# SWITCHING.net
KiCad netlist of a schematic drawn in Altium Designer
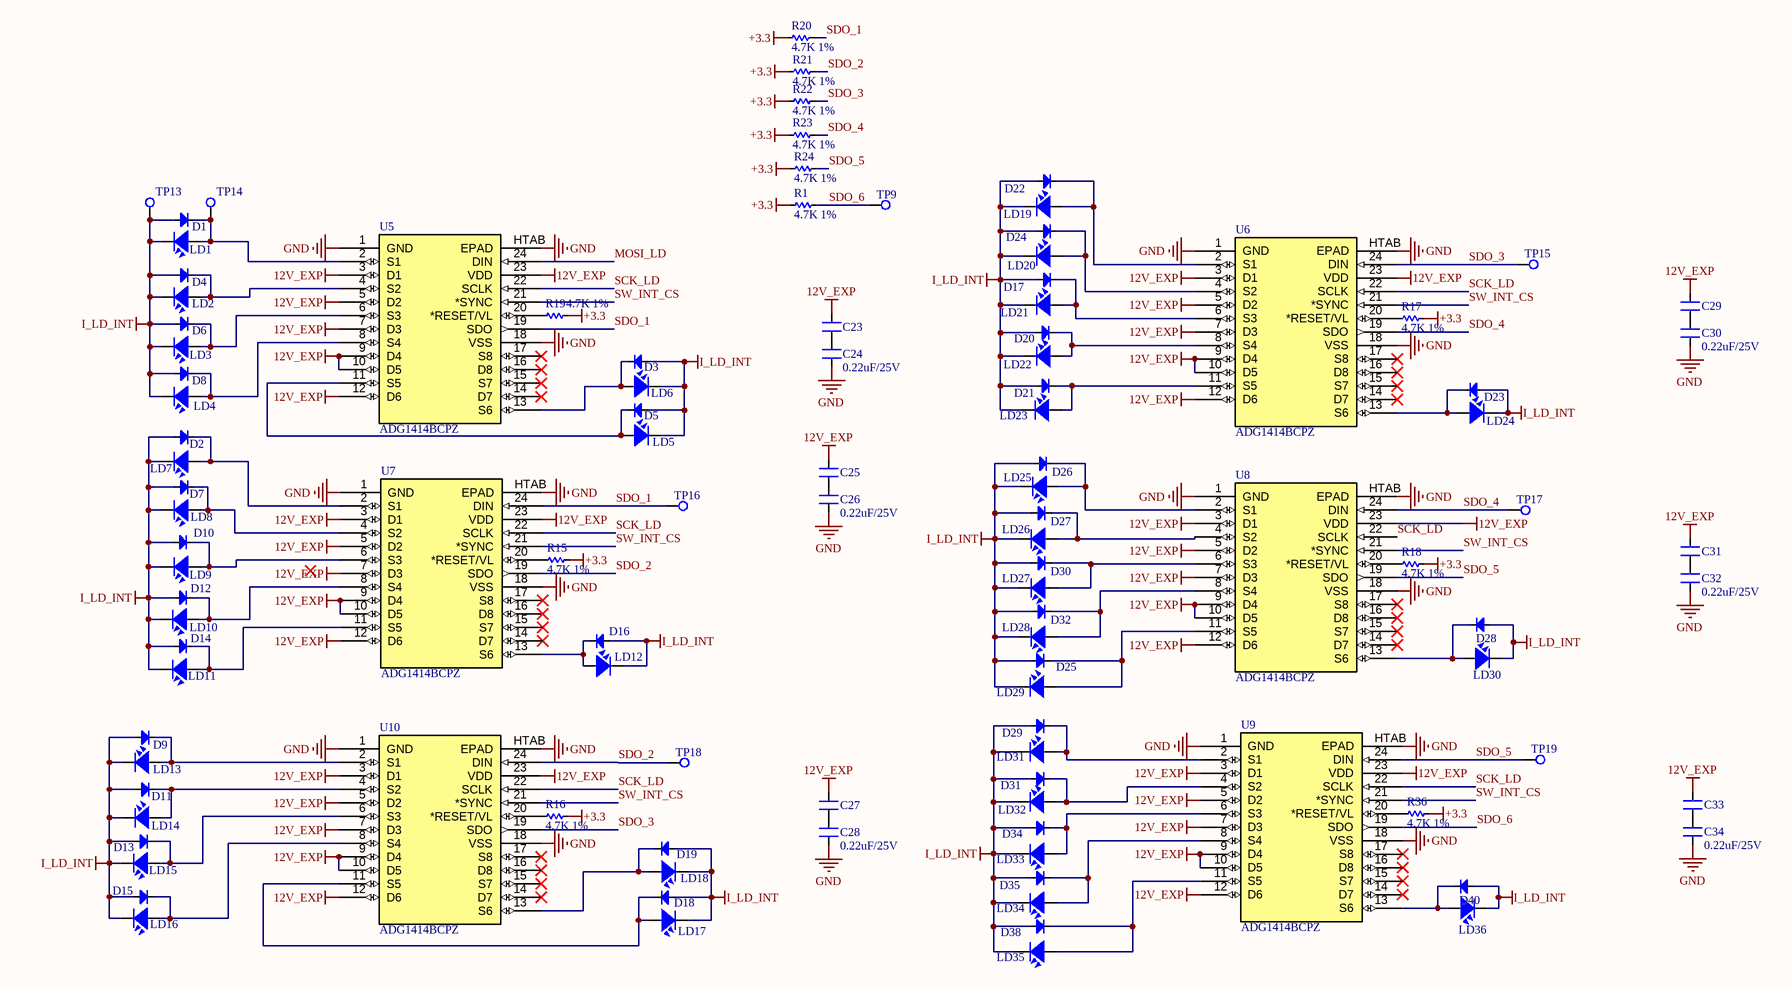
[diagram p0: SWITCHING.SchDoc]

(export (version "E")
  (design (tool "Eeschema 10.0.6"))
  (components
    (comp (ref "C23")
      (value "0.22uF/25V")
      (footprint "SM-0603")
      (description "0603")
      (libsource (lib "Capacitors") (part "CM"))
    )
    (comp (ref "C24")
      (value "0.22uF/25V")
      (footprint "SM-0603")
      (description "0603")
      (libsource (lib "Capacitors") (part "CM"))
    )
    (comp (ref "C25")
      (value "0.22uF/25V")
      (footprint "SM-0603")
      (description "0603")
      (libsource (lib "Capacitors") (part "CM"))
    )
    (comp (ref "C26")
      (value "0.22uF/25V")
      (footprint "SM-0603")
      (description "0603")
      (libsource (lib "Capacitors") (part "CM"))
    )
    (comp (ref "C27")
      (value "0.22uF/25V")
      (footprint "SM-0603")
      (description "0603")
      (libsource (lib "Capacitors") (part "CM"))
    )
    (comp (ref "C28")
      (value "0.22uF/25V")
      (footprint "SM-0603")
      (description "0603")
      (libsource (lib "Capacitors") (part "CM"))
    )
    (comp (ref "C29")
      (value "0.22uF/25V")
      (footprint "SM-0603")
      (description "0603")
      (libsource (lib "Capacitors") (part "CM"))
    )
    (comp (ref "C30")
      (value "0.22uF/25V")
      (footprint "SM-0603")
      (description "0603")
      (libsource (lib "Capacitors") (part "CM"))
    )
    (comp (ref "C31")
      (value "0.22uF/25V")
      (footprint "SM-0603")
      (description "0603")
      (libsource (lib "Capacitors") (part "CM"))
    )
    (comp (ref "C32")
      (value "0.22uF/25V")
      (footprint "SM-0603")
      (description "0603")
      (libsource (lib "Capacitors") (part "CM"))
    )
    (comp (ref "C33")
      (value "0.22uF/25V")
      (footprint "SM-0603")
      (description "0603")
      (libsource (lib "Capacitors") (part "CM"))
    )
    (comp (ref "C34")
      (value "0.22uF/25V")
      (footprint "SM-0603")
      (description "0603")
      (libsource (lib "Capacitors") (part "CM"))
    )
    (comp (ref "D1")
      (value "1N4148W-TP")
      (footprint "SOD23")
      (description "DIODE GEN PURP 100V 150MA SOD123")
      (fields (field (name "PUBLISHER") "Altium Limited"))
      (libsource (lib "Library") (part "Diode SMD"))
    )
    (comp (ref "D2")
      (value "1N4148W-TP")
      (footprint "SOD23")
      (description "DIODE GEN PURP 100V 150MA SOD123")
      (fields (field (name "PUBLISHER") "Altium Limited"))
      (libsource (lib "Library") (part "Diode SMD"))
    )
    (comp (ref "D3")
      (value "1N4148W-TP")
      (footprint "SOD23")
      (description "DIODE GEN PURP 100V 150MA SOD123")
      (fields (field (name "PUBLISHER") "Altium Limited"))
      (libsource (lib "Library") (part "Diode SMD"))
    )
    (comp (ref "D4")
      (value "1N4148W-TP")
      (footprint "SOD23")
      (description "DIODE GEN PURP 100V 150MA SOD123")
      (fields (field (name "PUBLISHER") "Altium Limited"))
      (libsource (lib "Library") (part "Diode SMD"))
    )
    (comp (ref "D5")
      (value "1N4148W-TP")
      (footprint "SOD23")
      (description "DIODE GEN PURP 100V 150MA SOD123")
      (fields (field (name "PUBLISHER") "Altium Limited"))
      (libsource (lib "Library") (part "Diode SMD"))
    )
    (comp (ref "D6")
      (value "1N4148W-TP")
      (footprint "SOD23")
      (description "DIODE GEN PURP 100V 150MA SOD123")
      (fields (field (name "PUBLISHER") "Altium Limited"))
      (libsource (lib "Library") (part "Diode SMD"))
    )
    (comp (ref "D7")
      (value "1N4148W-TP")
      (footprint "SOD23")
      (description "DIODE GEN PURP 100V 150MA SOD123")
      (fields (field (name "PUBLISHER") "Altium Limited"))
      (libsource (lib "Library") (part "Diode SMD"))
    )
    (comp (ref "D8")
      (value "1N4148W-TP")
      (footprint "SOD23")
      (description "DIODE GEN PURP 100V 150MA SOD123")
      (fields (field (name "PUBLISHER") "Altium Limited"))
      (libsource (lib "Library") (part "Diode SMD"))
    )
    (comp (ref "D9")
      (value "1N4148W-TP")
      (footprint "SOD23")
      (description "DIODE GEN PURP 100V 150MA SOD123")
      (fields (field (name "PUBLISHER") "Altium Limited"))
      (libsource (lib "Library") (part "Diode SMD"))
    )
    (comp (ref "D10")
      (value "1N4148W-TP")
      (footprint "SOD23")
      (description "DIODE GEN PURP 100V 150MA SOD123")
      (fields (field (name "PUBLISHER") "Altium Limited"))
      (libsource (lib "Library") (part "Diode SMD"))
    )
    (comp (ref "D11")
      (value "1N4148W-TP")
      (footprint "SOD23")
      (description "DIODE GEN PURP 100V 150MA SOD123")
      (fields (field (name "PUBLISHER") "Altium Limited"))
      (libsource (lib "Library") (part "Diode SMD"))
    )
    (comp (ref "D12")
      (value "1N4148W-TP")
      (footprint "SOD23")
      (description "DIODE GEN PURP 100V 150MA SOD123")
      (fields (field (name "PUBLISHER") "Altium Limited"))
      (libsource (lib "Library") (part "Diode SMD"))
    )
    (comp (ref "D13")
      (value "1N4148W-TP")
      (footprint "SOD23")
      (description "DIODE GEN PURP 100V 150MA SOD123")
      (fields (field (name "PUBLISHER") "Altium Limited"))
      (libsource (lib "Library") (part "Diode SMD"))
    )
    (comp (ref "D14")
      (value "1N4148W-TP")
      (footprint "SOD23")
      (description "DIODE GEN PURP 100V 150MA SOD123")
      (fields (field (name "PUBLISHER") "Altium Limited"))
      (libsource (lib "Library") (part "Diode SMD"))
    )
    (comp (ref "D15")
      (value "1N4148W-TP")
      (footprint "SOD23")
      (description "DIODE GEN PURP 100V 150MA SOD123")
      (fields (field (name "PUBLISHER") "Altium Limited"))
      (libsource (lib "Library") (part "Diode SMD"))
    )
    (comp (ref "D16")
      (value "1N4148W-TP")
      (footprint "SOD23")
      (description "DIODE GEN PURP 100V 150MA SOD123")
      (fields (field (name "PUBLISHER") "Altium Limited"))
      (libsource (lib "Library") (part "Diode SMD"))
    )
    (comp (ref "D17")
      (value "1N4148W-TP")
      (footprint "SOD23")
      (description "DIODE GEN PURP 100V 150MA SOD123")
      (fields (field (name "PUBLISHER") "Altium Limited"))
      (libsource (lib "Library") (part "Diode SMD"))
    )
    (comp (ref "D18")
      (value "1N4148W-TP")
      (footprint "SOD23")
      (description "DIODE GEN PURP 100V 150MA SOD123")
      (fields (field (name "PUBLISHER") "Altium Limited"))
      (libsource (lib "Library") (part "Diode SMD"))
    )
    (comp (ref "D19")
      (value "1N4148W-TP")
      (footprint "SOD23")
      (description "DIODE GEN PURP 100V 150MA SOD123")
      (fields (field (name "PUBLISHER") "Altium Limited"))
      (libsource (lib "Library") (part "Diode SMD"))
    )
    (comp (ref "D20")
      (value "1N4148W-TP")
      (footprint "SOD23")
      (description "DIODE GEN PURP 100V 150MA SOD123")
      (fields (field (name "PUBLISHER") "Altium Limited"))
      (libsource (lib "Library") (part "Diode SMD"))
    )
    (comp (ref "D21")
      (value "1N4148W-TP")
      (footprint "SOD23")
      (description "DIODE GEN PURP 100V 150MA SOD123")
      (fields (field (name "PUBLISHER") "Altium Limited"))
      (libsource (lib "Library") (part "Diode SMD"))
    )
    (comp (ref "D22")
      (value "1N4148W-TP")
      (footprint "SOD23")
      (description "DIODE GEN PURP 100V 150MA SOD123")
      (fields (field (name "PUBLISHER") "Altium Limited"))
      (libsource (lib "Library") (part "Diode SMD"))
    )
    (comp (ref "D23")
      (value "1N4148W-TP")
      (footprint "SOD23")
      (description "DIODE GEN PURP 100V 150MA SOD123")
      (fields (field (name "PUBLISHER") "Altium Limited"))
      (libsource (lib "Library") (part "Diode SMD"))
    )
    (comp (ref "D24")
      (value "1N4148W-TP")
      (footprint "SOD23")
      (description "DIODE GEN PURP 100V 150MA SOD123")
      (fields (field (name "PUBLISHER") "Altium Limited"))
      (libsource (lib "Library") (part "Diode SMD"))
    )
    (comp (ref "D25")
      (value "1N4148W-TP")
      (footprint "SOD23")
      (description "DIODE GEN PURP 100V 150MA SOD123")
      (fields (field (name "PUBLISHER") "Altium Limited"))
      (libsource (lib "Library") (part "Diode SMD"))
    )
    (comp (ref "D26")
      (value "1N4148W-TP")
      (footprint "SOD23")
      (description "DIODE GEN PURP 100V 150MA SOD123")
      (fields (field (name "PUBLISHER") "Altium Limited"))
      (libsource (lib "Library") (part "Diode SMD"))
    )
    (comp (ref "D27")
      (value "1N4148W-TP")
      (footprint "SOD23")
      (description "DIODE GEN PURP 100V 150MA SOD123")
      (fields (field (name "PUBLISHER") "Altium Limited"))
      (libsource (lib "Library") (part "Diode SMD"))
    )
    (comp (ref "D28")
      (value "1N4148W-TP")
      (footprint "SOD23")
      (description "DIODE GEN PURP 100V 150MA SOD123")
      (fields (field (name "PUBLISHER") "Altium Limited"))
      (libsource (lib "Library") (part "Diode SMD"))
    )
    (comp (ref "D29")
      (value "1N4148W-TP")
      (footprint "SOD23")
      (description "DIODE GEN PURP 100V 150MA SOD123")
      (fields (field (name "PUBLISHER") "Altium Limited"))
      (libsource (lib "Library") (part "Diode SMD"))
    )
    (comp (ref "D30")
      (value "1N4148W-TP")
      (footprint "SOD23")
      (description "DIODE GEN PURP 100V 150MA SOD123")
      (fields (field (name "PUBLISHER") "Altium Limited"))
      (libsource (lib "Library") (part "Diode SMD"))
    )
    (comp (ref "D31")
      (value "1N4148W-TP")
      (footprint "SOD23")
      (description "DIODE GEN PURP 100V 150MA SOD123")
      (fields (field (name "PUBLISHER") "Altium Limited"))
      (libsource (lib "Library") (part "Diode SMD"))
    )
    (comp (ref "D32")
      (value "1N4148W-TP")
      (footprint "SOD23")
      (description "DIODE GEN PURP 100V 150MA SOD123")
      (fields (field (name "PUBLISHER") "Altium Limited"))
      (libsource (lib "Library") (part "Diode SMD"))
    )
    (comp (ref "D34")
      (value "1N4148W-TP")
      (footprint "SOD23")
      (description "DIODE GEN PURP 100V 150MA SOD123")
      (fields (field (name "PUBLISHER") "Altium Limited"))
      (libsource (lib "Library") (part "Diode SMD"))
    )
    (comp (ref "D35")
      (value "1N4148W-TP")
      (footprint "SOD23")
      (description "DIODE GEN PURP 100V 150MA SOD123")
      (fields (field (name "PUBLISHER") "Altium Limited"))
      (libsource (lib "Library") (part "Diode SMD"))
    )
    (comp (ref "D38")
      (value "1N4148W-TP")
      (footprint "SOD23")
      (description "DIODE GEN PURP 100V 150MA SOD123")
      (fields (field (name "PUBLISHER") "Altium Limited"))
      (libsource (lib "Library") (part "Diode SMD"))
    )
    (comp (ref "D40")
      (value "1N4148W-TP")
      (footprint "SOD23")
      (description "DIODE GEN PURP 100V 150MA SOD123")
      (fields (field (name "PUBLISHER") "Altium Limited"))
      (libsource (lib "Library") (part "Diode SMD"))
    )
    (comp (ref "LD1")
      (value "LaserDiode")
      (footprint "LASER_SOCKET")
      (libsource (lib "Library_HUNG") (part "LD"))
    )
    (comp (ref "LD2")
      (value "LaserDiode")
      (footprint "LASER_SOCKET")
      (libsource (lib "Library_HUNG") (part "LD"))
    )
    (comp (ref "LD3")
      (value "LaserDiode")
      (footprint "LASER_SOCKET")
      (libsource (lib "Library_HUNG") (part "LD"))
    )
    (comp (ref "LD4")
      (value "LaserDiode")
      (footprint "LASER_SOCKET")
      (libsource (lib "Library_HUNG") (part "LD"))
    )
    (comp (ref "LD5")
      (value "LaserDiode")
      (footprint "LASER_SOCKET")
      (libsource (lib "Library_HUNG") (part "LD"))
    )
    (comp (ref "LD6")
      (value "LaserDiode")
      (footprint "LASER_SOCKET")
      (libsource (lib "Library_HUNG") (part "LD"))
    )
    (comp (ref "LD7")
      (value "LaserDiode")
      (footprint "LASER_SOCKET")
      (libsource (lib "Library_HUNG") (part "LD"))
    )
    (comp (ref "LD8")
      (value "LaserDiode")
      (footprint "LASER_SOCKET")
      (libsource (lib "Library_HUNG") (part "LD"))
    )
    (comp (ref "LD9")
      (value "LaserDiode")
      (footprint "LASER_SOCKET")
      (libsource (lib "Library_HUNG") (part "LD"))
    )
    (comp (ref "LD10")
      (value "LaserDiode")
      (footprint "LASER_SOCKET")
      (libsource (lib "Library_HUNG") (part "LD"))
    )
    (comp (ref "LD11")
      (value "LaserDiode")
      (footprint "LASER_SOCKET")
      (libsource (lib "Library_HUNG") (part "LD"))
    )
    (comp (ref "LD12")
      (value "LaserDiode")
      (footprint "LASER_SOCKET")
      (libsource (lib "Library_HUNG") (part "LD"))
    )
    (comp (ref "LD13")
      (value "LaserDiode")
      (footprint "LASER_SOCKET")
      (libsource (lib "Library_HUNG") (part "LD"))
    )
    (comp (ref "LD14")
      (value "LaserDiode")
      (footprint "LASER_SOCKET")
      (libsource (lib "Library_HUNG") (part "LD"))
    )
    (comp (ref "LD15")
      (value "LaserDiode")
      (footprint "LASER_SOCKET")
      (libsource (lib "Library_HUNG") (part "LD"))
    )
    (comp (ref "LD16")
      (value "LaserDiode")
      (footprint "LASER_SOCKET")
      (libsource (lib "Library_HUNG") (part "LD"))
    )
    (comp (ref "LD17")
      (value "LaserDiode")
      (footprint "LASER_SOCKET")
      (libsource (lib "Library_HUNG") (part "LD"))
    )
    (comp (ref "LD18")
      (value "LaserDiode")
      (footprint "LASER_SOCKET")
      (libsource (lib "Library_HUNG") (part "LD"))
    )
    (comp (ref "LD19")
      (value "LaserDiode")
      (footprint "LASER_SOCKET")
      (libsource (lib "Library_HUNG") (part "LD"))
    )
    (comp (ref "LD20")
      (value "LaserDiode")
      (footprint "LASER_SOCKET")
      (libsource (lib "Library_HUNG") (part "LD"))
    )
    (comp (ref "LD21")
      (value "LaserDiode")
      (footprint "LASER_SOCKET")
      (libsource (lib "Library_HUNG") (part "LD"))
    )
    (comp (ref "LD22")
      (value "LaserDiode")
      (footprint "LASER_SOCKET")
      (libsource (lib "Library_HUNG") (part "LD"))
    )
    (comp (ref "LD23")
      (value "LaserDiode")
      (footprint "LASER_SOCKET")
      (libsource (lib "Library_HUNG") (part "LD"))
    )
    (comp (ref "LD24")
      (value "LaserDiode")
      (footprint "LASER_SOCKET")
      (libsource (lib "Library_HUNG") (part "LD"))
    )
    (comp (ref "LD25")
      (value "LaserDiode")
      (footprint "LASER_SOCKET")
      (libsource (lib "Library_HUNG") (part "LD"))
    )
    (comp (ref "LD26")
      (value "LaserDiode")
      (footprint "LASER_SOCKET")
      (libsource (lib "Library_HUNG") (part "LD"))
    )
    (comp (ref "LD27")
      (value "LaserDiode")
      (footprint "LASER_SOCKET")
      (libsource (lib "Library_HUNG") (part "LD"))
    )
    (comp (ref "LD28")
      (value "LaserDiode")
      (footprint "LASER_SOCKET")
      (libsource (lib "Library_HUNG") (part "LD"))
    )
    (comp (ref "LD29")
      (value "LaserDiode")
      (footprint "LASER_SOCKET")
      (libsource (lib "Library_HUNG") (part "LD"))
    )
    (comp (ref "LD30")
      (value "LaserDiode")
      (footprint "LASER_SOCKET")
      (libsource (lib "Library_HUNG") (part "LD"))
    )
    (comp (ref "LD31")
      (value "LaserDiode")
      (footprint "LASER_SOCKET")
      (libsource (lib "Library_HUNG") (part "LD"))
    )
    (comp (ref "LD32")
      (value "LaserDiode")
      (footprint "LASER_SOCKET")
      (libsource (lib "Library_HUNG") (part "LD"))
    )
    (comp (ref "LD33")
      (value "LaserDiode")
      (footprint "LASER_SOCKET")
      (libsource (lib "Library_HUNG") (part "LD"))
    )
    (comp (ref "LD34")
      (value "LaserDiode")
      (footprint "LASER_SOCKET")
      (libsource (lib "Library_HUNG") (part "LD"))
    )
    (comp (ref "LD35")
      (value "LaserDiode")
      (footprint "LASER_SOCKET")
      (libsource (lib "Library_HUNG") (part "LD"))
    )
    (comp (ref "LD36")
      (value "LaserDiode")
      (footprint "LASER_SOCKET")
      (libsource (lib "Library_HUNG") (part "LD"))
    )
    (comp (ref "R1")
      (value "4.7K 1%")
      (footprint "RES-SMD-0603")
      (description "0603")
      (fields
        (field (name "MANUFACTURER") "Generic Components")
        (field (name "PUBLISHER") "Altium Hobart Technology Centre")
      )
      (libsource (lib "Library") (part "Res-SMD"))
    )
    (comp (ref "R15")
      (value "4.7K 1%")
      (footprint "RES-SMD-0603")
      (description "0603")
      (fields
        (field (name "MANUFACTURER") "Generic Components")
        (field (name "PUBLISHER") "Altium Hobart Technology Centre")
      )
      (libsource (lib "Library") (part "Res-SMD"))
    )
    (comp (ref "R16")
      (value "4.7K 1%")
      (footprint "RES-SMD-0603")
      (description "0603")
      (fields
        (field (name "MANUFACTURER") "Generic Components")
        (field (name "PUBLISHER") "Altium Hobart Technology Centre")
      )
      (libsource (lib "Library") (part "Res-SMD"))
    )
    (comp (ref "R17")
      (value "4.7K 1%")
      (footprint "RES-SMD-0603")
      (description "0603")
      (fields
        (field (name "MANUFACTURER") "Generic Components")
        (field (name "PUBLISHER") "Altium Hobart Technology Centre")
      )
      (libsource (lib "Library") (part "Res-SMD"))
    )
    (comp (ref "R18")
      (value "4.7K 1%")
      (footprint "RES-SMD-0603")
      (description "0603")
      (fields
        (field (name "MANUFACTURER") "Generic Components")
        (field (name "PUBLISHER") "Altium Hobart Technology Centre")
      )
      (libsource (lib "Library") (part "Res-SMD"))
    )
    (comp (ref "R19")
      (value "4.7K 1%")
      (footprint "RES-SMD-0603")
      (description "0603")
      (fields
        (field (name "MANUFACTURER") "Generic Components")
        (field (name "PUBLISHER") "Altium Hobart Technology Centre")
      )
      (libsource (lib "Library") (part "Res-SMD"))
    )
    (comp (ref "R20")
      (value "4.7K 1%")
      (footprint "RES-SMD-0603")
      (description "0603")
      (fields
        (field (name "MANUFACTURER") "Generic Components")
        (field (name "PUBLISHER") "Altium Hobart Technology Centre")
      )
      (libsource (lib "Library") (part "Res-SMD"))
    )
    (comp (ref "R21")
      (value "4.7K 1%")
      (footprint "RES-SMD-0603")
      (description "0603")
      (fields
        (field (name "MANUFACTURER") "Generic Components")
        (field (name "PUBLISHER") "Altium Hobart Technology Centre")
      )
      (libsource (lib "Library") (part "Res-SMD"))
    )
    (comp (ref "R22")
      (value "4.7K 1%")
      (footprint "RES-SMD-0603")
      (description "0603")
      (fields
        (field (name "MANUFACTURER") "Generic Components")
        (field (name "PUBLISHER") "Altium Hobart Technology Centre")
      )
      (libsource (lib "Library") (part "Res-SMD"))
    )
    (comp (ref "R23")
      (value "4.7K 1%")
      (footprint "RES-SMD-0603")
      (description "0603")
      (fields
        (field (name "MANUFACTURER") "Generic Components")
        (field (name "PUBLISHER") "Altium Hobart Technology Centre")
      )
      (libsource (lib "Library") (part "Res-SMD"))
    )
    (comp (ref "R24")
      (value "4.7K 1%")
      (footprint "RES-SMD-0603")
      (description "0603")
      (fields
        (field (name "MANUFACTURER") "Generic Components")
        (field (name "PUBLISHER") "Altium Hobart Technology Centre")
      )
      (libsource (lib "Library") (part "Res-SMD"))
    )
    (comp (ref "R36")
      (value "4.7K 1%")
      (footprint "RES-SMD-0603")
      (description "0603")
      (fields
        (field (name "MANUFACTURER") "Generic Components")
        (field (name "PUBLISHER") "Altium Hobart Technology Centre")
      )
      (libsource (lib "Library") (part "Res-SMD"))
    )
    (comp (ref "TP9")
      (value "Test_Point")
      (footprint "TESTPOINT")
      (libsource (lib "Library_HUNG") (part "Test_Point"))
    )
    (comp (ref "TP13")
      (value "Test_Point")
      (footprint "TESTPOINT")
      (libsource (lib "Library_HUNG") (part "Test_Point"))
    )
    (comp (ref "TP14")
      (value "Test_Point")
      (footprint "TESTPOINT")
      (libsource (lib "Library_HUNG") (part "Test_Point"))
    )
    (comp (ref "TP15")
      (value "Test_Point")
      (footprint "TESTPOINT")
      (libsource (lib "Library_HUNG") (part "Test_Point"))
    )
    (comp (ref "TP16")
      (value "Test_Point")
      (footprint "TESTPOINT")
      (libsource (lib "Library_HUNG") (part "Test_Point"))
    )
    (comp (ref "TP17")
      (value "Test_Point")
      (footprint "TESTPOINT")
      (libsource (lib "Library_HUNG") (part "Test_Point"))
    )
    (comp (ref "TP18")
      (value "Test_Point")
      (footprint "TESTPOINT")
      (libsource (lib "Library_HUNG") (part "Test_Point"))
    )
    (comp (ref "TP19")
      (value "Test_Point")
      (footprint "TESTPOINT")
      (libsource (lib "Library_HUNG") (part "Test_Point"))
    )
    (comp (ref "U5")
      (value "ADG1414BCPZ")
      (footprint "ADG1414BCPZ")
      (description "IC SW SPST-NOX8 11.5OHM 24LFCSP")
      (libsource (lib "Library_HUNG") (part "ADG1414"))
    )
    (comp (ref "U6")
      (value "ADG1414BCPZ")
      (footprint "ADG1414BCPZ")
      (description "IC SW SPST-NOX8 11.5OHM 24LFCSP")
      (libsource (lib "Library_HUNG") (part "ADG1414"))
    )
    (comp (ref "U7")
      (value "ADG1414BCPZ")
      (footprint "ADG1414BCPZ")
      (description "IC SW SPST-NOX8 11.5OHM 24LFCSP")
      (libsource (lib "Library_HUNG") (part "ADG1414"))
    )
    (comp (ref "U8")
      (value "ADG1414BCPZ")
      (footprint "ADG1414BCPZ")
      (description "IC SW SPST-NOX8 11.5OHM 24LFCSP")
      (libsource (lib "Library_HUNG") (part "ADG1414"))
    )
    (comp (ref "U9")
      (value "ADG1414BCPZ")
      (footprint "ADG1414BCPZ")
      (description "IC SW SPST-NOX8 11.5OHM 24LFCSP")
      (libsource (lib "Library_HUNG") (part "ADG1414"))
    )
    (comp (ref "U10")
      (value "ADG1414BCPZ")
      (footprint "ADG1414BCPZ")
      (description "IC SW SPST-NOX8 11.5OHM 24LFCSP")
      (libsource (lib "Library_HUNG") (part "ADG1414"))
    )
  )
  (nets
    (net (code "1") (name "+3.3") (class "Default")
      (node (ref "R1") (pin "2") (pinfunction "2_2") (pintype "passive"))
      (node (ref "R15") (pin "2") (pinfunction "2_2") (pintype "passive"))
      (node (ref "R16") (pin "2") (pinfunction "2_2") (pintype "passive"))
      (node (ref "R17") (pin "2") (pinfunction "2_2") (pintype "passive"))
      (node (ref "R18") (pin "2") (pinfunction "2_2") (pintype "passive"))
      (node (ref "R19") (pin "2") (pinfunction "2_2") (pintype "passive"))
      (node (ref "R20") (pin "2") (pinfunction "2_2") (pintype "passive"))
      (node (ref "R21") (pin "2") (pinfunction "2_2") (pintype "passive"))
      (node (ref "R22") (pin "2") (pinfunction "2_2") (pintype "passive"))
      (node (ref "R23") (pin "2") (pinfunction "2_2") (pintype "passive"))
      (node (ref "R24") (pin "2") (pinfunction "2_2") (pintype "passive"))
      (node (ref "R36") (pin "2") (pinfunction "2_2") (pintype "passive"))
    )
    (net (code "2") (name "/MOSI_LD") (class "Default")
      (node (ref "U5") (pin "24") (pinfunction "DIN_24") (pintype "input"))
    )
    (net (code "3") (name "/SCK_LD") (class "Default")
      (node (ref "U10") (pin "22") (pinfunction "SCLK_22") (pintype "input"))
      (node (ref "U5") (pin "22") (pinfunction "SCLK_22") (pintype "input"))
      (node (ref "U6") (pin "22") (pinfunction "SCLK_22") (pintype "input"))
      (node (ref "U7") (pin "22") (pinfunction "SCLK_22") (pintype "input"))
      (node (ref "U8") (pin "22") (pinfunction "SCLK_22") (pintype "input"))
      (node (ref "U9") (pin "22") (pinfunction "SCLK_22") (pintype "input"))
    )
    (net (code "4") (name "/SDO_1") (class "Default")
      (node (ref "R20") (pin "1") (pinfunction "1_1") (pintype "passive"))
      (node (ref "TP16") (pin "1") (pintype "power_in"))
      (node (ref "U5") (pin "19") (pinfunction "SDO_19") (pintype "output"))
      (node (ref "U7") (pin "24") (pinfunction "DIN_24") (pintype "input"))
    )
    (net (code "5") (name "/SDO_2") (class "Default")
      (node (ref "R21") (pin "1") (pinfunction "1_1") (pintype "passive"))
      (node (ref "TP18") (pin "1") (pintype "power_in"))
      (node (ref "U10") (pin "24") (pinfunction "DIN_24") (pintype "input"))
      (node (ref "U7") (pin "19") (pinfunction "SDO_19") (pintype "output"))
    )
    (net (code "6") (name "/SDO_3") (class "Default")
      (node (ref "R22") (pin "1") (pinfunction "1_1") (pintype "passive"))
      (node (ref "TP15") (pin "1") (pintype "power_in"))
      (node (ref "U10") (pin "19") (pinfunction "SDO_19") (pintype "output"))
      (node (ref "U6") (pin "24") (pinfunction "DIN_24") (pintype "input"))
    )
    (net (code "7") (name "/SDO_4") (class "Default")
      (node (ref "R23") (pin "1") (pinfunction "1_1") (pintype "passive"))
      (node (ref "TP17") (pin "1") (pintype "power_in"))
      (node (ref "U6") (pin "19") (pinfunction "SDO_19") (pintype "output"))
      (node (ref "U8") (pin "24") (pinfunction "DIN_24") (pintype "input"))
    )
    (net (code "8") (name "/SDO_5") (class "Default")
      (node (ref "R24") (pin "1") (pinfunction "1_1") (pintype "passive"))
      (node (ref "TP19") (pin "1") (pintype "power_in"))
      (node (ref "U8") (pin "19") (pinfunction "SDO_19") (pintype "output"))
      (node (ref "U9") (pin "24") (pinfunction "DIN_24") (pintype "input"))
    )
    (net (code "9") (name "/SDO_6") (class "Default")
      (node (ref "R1") (pin "1") (pinfunction "1_1") (pintype "passive"))
      (node (ref "TP9") (pin "1") (pintype "power_in"))
      (node (ref "U9") (pin "19") (pinfunction "SDO_19") (pintype "output"))
    )
    (net (code "10") (name "/SW_INT_CS") (class "Default")
      (node (ref "U10") (pin "21") (pinfunction "*SYNC_21") (pintype "input"))
      (node (ref "U5") (pin "21") (pinfunction "*SYNC_21") (pintype "input"))
      (node (ref "U6") (pin "21") (pinfunction "*SYNC_21") (pintype "input"))
      (node (ref "U7") (pin "21") (pinfunction "*SYNC_21") (pintype "input"))
      (node (ref "U8") (pin "21") (pinfunction "*SYNC_21") (pintype "input"))
      (node (ref "U9") (pin "21") (pinfunction "*SYNC_21") (pintype "input"))
    )
    (net (code "11") (name "12V_EXP") (class "Default")
      (node (ref "C23") (pin "2") (pinfunction "2_2") (pintype "passive"))
      (node (ref "C25") (pin "2") (pinfunction "2_2") (pintype "passive"))
      (node (ref "C27") (pin "2") (pinfunction "2_2") (pintype "passive"))
      (node (ref "C29") (pin "2") (pinfunction "2_2") (pintype "passive"))
      (node (ref "C31") (pin "2") (pinfunction "2_2") (pintype "passive"))
      (node (ref "C33") (pin "2") (pinfunction "2_2") (pintype "passive"))
      (node (ref "U10") (pin "10") (pinfunction "D5_10") (pintype "bidirectional"))
      (node (ref "U10") (pin "12") (pinfunction "D6_12") (pintype "bidirectional"))
      (node (ref "U10") (pin "23") (pinfunction "VDD_23") (pintype "power_in"))
      (node (ref "U10") (pin "3") (pinfunction "D1_3") (pintype "bidirectional"))
      (node (ref "U10") (pin "5") (pinfunction "D2_5") (pintype "bidirectional"))
      (node (ref "U10") (pin "7") (pinfunction "D3_7") (pintype "bidirectional"))
      (node (ref "U10") (pin "9") (pinfunction "D4_9") (pintype "bidirectional"))
      (node (ref "U5") (pin "10") (pinfunction "D5_10") (pintype "bidirectional"))
      (node (ref "U5") (pin "12") (pinfunction "D6_12") (pintype "bidirectional"))
      (node (ref "U5") (pin "23") (pinfunction "VDD_23") (pintype "power_in"))
      (node (ref "U5") (pin "3") (pinfunction "D1_3") (pintype "bidirectional"))
      (node (ref "U5") (pin "5") (pinfunction "D2_5") (pintype "bidirectional"))
      (node (ref "U5") (pin "7") (pinfunction "D3_7") (pintype "bidirectional"))
      (node (ref "U5") (pin "9") (pinfunction "D4_9") (pintype "bidirectional"))
      (node (ref "U6") (pin "10") (pinfunction "D5_10") (pintype "bidirectional"))
      (node (ref "U6") (pin "12") (pinfunction "D6_12") (pintype "bidirectional"))
      (node (ref "U6") (pin "23") (pinfunction "VDD_23") (pintype "power_in"))
      (node (ref "U6") (pin "3") (pinfunction "D1_3") (pintype "bidirectional"))
      (node (ref "U6") (pin "5") (pinfunction "D2_5") (pintype "bidirectional"))
      (node (ref "U6") (pin "7") (pinfunction "D3_7") (pintype "bidirectional"))
      (node (ref "U6") (pin "9") (pinfunction "D4_9") (pintype "bidirectional"))
      (node (ref "U7") (pin "10") (pinfunction "D5_10") (pintype "bidirectional"))
      (node (ref "U7") (pin "12") (pinfunction "D6_12") (pintype "bidirectional"))
      (node (ref "U7") (pin "23") (pinfunction "VDD_23") (pintype "power_in"))
      (node (ref "U7") (pin "3") (pinfunction "D1_3") (pintype "bidirectional"))
      (node (ref "U7") (pin "5") (pinfunction "D2_5") (pintype "bidirectional"))
      (node (ref "U7") (pin "7") (pinfunction "D3_7") (pintype "bidirectional"))
      (node (ref "U7") (pin "9") (pinfunction "D4_9") (pintype "bidirectional"))
      (node (ref "U8") (pin "10") (pinfunction "D5_10") (pintype "bidirectional"))
      (node (ref "U8") (pin "12") (pinfunction "D6_12") (pintype "bidirectional"))
      (node (ref "U8") (pin "23") (pinfunction "VDD_23") (pintype "power_in"))
      (node (ref "U8") (pin "3") (pinfunction "D1_3") (pintype "bidirectional"))
      (node (ref "U8") (pin "5") (pinfunction "D2_5") (pintype "bidirectional"))
      (node (ref "U8") (pin "7") (pinfunction "D3_7") (pintype "bidirectional"))
      (node (ref "U8") (pin "9") (pinfunction "D4_9") (pintype "bidirectional"))
      (node (ref "U9") (pin "10") (pinfunction "D5_10") (pintype "bidirectional"))
      (node (ref "U9") (pin "12") (pinfunction "D6_12") (pintype "bidirectional"))
      (node (ref "U9") (pin "23") (pinfunction "VDD_23") (pintype "power_in"))
      (node (ref "U9") (pin "3") (pinfunction "D1_3") (pintype "bidirectional"))
      (node (ref "U9") (pin "5") (pinfunction "D2_5") (pintype "bidirectional"))
      (node (ref "U9") (pin "7") (pinfunction "D3_7") (pintype "bidirectional"))
      (node (ref "U9") (pin "9") (pinfunction "D4_9") (pintype "bidirectional"))
    )
    (net (code "12") (name "GND") (class "Default")
      (node (ref "C24") (pin "1") (pinfunction "1_1") (pintype "passive"))
      (node (ref "C26") (pin "1") (pinfunction "1_1") (pintype "passive"))
      (node (ref "C28") (pin "1") (pinfunction "1_1") (pintype "passive"))
      (node (ref "C30") (pin "1") (pinfunction "1_1") (pintype "passive"))
      (node (ref "C32") (pin "1") (pinfunction "1_1") (pintype "passive"))
      (node (ref "C34") (pin "1") (pinfunction "1_1") (pintype "passive"))
      (node (ref "U10") (pin "1") (pinfunction "GND_1") (pintype "power_in"))
      (node (ref "U10") (pin "18") (pinfunction "VSS_18") (pintype "power_in"))
      (node (ref "U10") (pin "HTAB") (pinfunction "EPAD_HTAB") (pintype "passive"))
      (node (ref "U5") (pin "1") (pinfunction "GND_1") (pintype "power_in"))
      (node (ref "U5") (pin "18") (pinfunction "VSS_18") (pintype "power_in"))
      (node (ref "U5") (pin "HTAB") (pinfunction "EPAD_HTAB") (pintype "passive"))
      (node (ref "U6") (pin "1") (pinfunction "GND_1") (pintype "power_in"))
      (node (ref "U6") (pin "18") (pinfunction "VSS_18") (pintype "power_in"))
      (node (ref "U6") (pin "HTAB") (pinfunction "EPAD_HTAB") (pintype "passive"))
      (node (ref "U7") (pin "1") (pinfunction "GND_1") (pintype "power_in"))
      (node (ref "U7") (pin "18") (pinfunction "VSS_18") (pintype "power_in"))
      (node (ref "U7") (pin "HTAB") (pinfunction "EPAD_HTAB") (pintype "passive"))
      (node (ref "U8") (pin "1") (pinfunction "GND_1") (pintype "power_in"))
      (node (ref "U8") (pin "18") (pinfunction "VSS_18") (pintype "power_in"))
      (node (ref "U8") (pin "HTAB") (pinfunction "EPAD_HTAB") (pintype "passive"))
      (node (ref "U9") (pin "1") (pinfunction "GND_1") (pintype "power_in"))
      (node (ref "U9") (pin "18") (pinfunction "VSS_18") (pintype "power_in"))
      (node (ref "U9") (pin "HTAB") (pinfunction "EPAD_HTAB") (pintype "passive"))
    )
    (net (code "13") (name "I_LD_INT") (class "Default")
      (node (ref "D1") (pin "1") (pinfunction "A_1") (pintype "passive"))
      (node (ref "D10") (pin "1") (pinfunction "A_1") (pintype "passive"))
      (node (ref "D11") (pin "1") (pinfunction "A_1") (pintype "passive"))
      (node (ref "D12") (pin "1") (pinfunction "A_1") (pintype "passive"))
      (node (ref "D13") (pin "1") (pinfunction "A_1") (pintype "passive"))
      (node (ref "D14") (pin "1") (pinfunction "A_1") (pintype "passive"))
      (node (ref "D15") (pin "1") (pinfunction "A_1") (pintype "passive"))
      (node (ref "D16") (pin "1") (pinfunction "A_1") (pintype "passive"))
      (node (ref "D17") (pin "1") (pinfunction "A_1") (pintype "passive"))
      (node (ref "D18") (pin "1") (pinfunction "A_1") (pintype "passive"))
      (node (ref "D19") (pin "1") (pinfunction "A_1") (pintype "passive"))
      (node (ref "D2") (pin "1") (pinfunction "A_1") (pintype "passive"))
      (node (ref "D20") (pin "1") (pinfunction "A_1") (pintype "passive"))
      (node (ref "D21") (pin "1") (pinfunction "A_1") (pintype "passive"))
      (node (ref "D22") (pin "1") (pinfunction "A_1") (pintype "passive"))
      (node (ref "D23") (pin "1") (pinfunction "A_1") (pintype "passive"))
      (node (ref "D24") (pin "1") (pinfunction "A_1") (pintype "passive"))
      (node (ref "D25") (pin "1") (pinfunction "A_1") (pintype "passive"))
      (node (ref "D26") (pin "1") (pinfunction "A_1") (pintype "passive"))
      (node (ref "D27") (pin "1") (pinfunction "A_1") (pintype "passive"))
      (node (ref "D28") (pin "1") (pinfunction "A_1") (pintype "passive"))
      (node (ref "D29") (pin "1") (pinfunction "A_1") (pintype "passive"))
      (node (ref "D3") (pin "1") (pinfunction "A_1") (pintype "passive"))
      (node (ref "D30") (pin "1") (pinfunction "A_1") (pintype "passive"))
      (node (ref "D31") (pin "1") (pinfunction "A_1") (pintype "passive"))
      (node (ref "D32") (pin "1") (pinfunction "A_1") (pintype "passive"))
      (node (ref "D34") (pin "1") (pinfunction "A_1") (pintype "passive"))
      (node (ref "D35") (pin "1") (pinfunction "A_1") (pintype "passive"))
      (node (ref "D38") (pin "1") (pinfunction "A_1") (pintype "passive"))
      (node (ref "D4") (pin "1") (pinfunction "A_1") (pintype "passive"))
      (node (ref "D40") (pin "1") (pinfunction "A_1") (pintype "passive"))
      (node (ref "D5") (pin "1") (pinfunction "A_1") (pintype "passive"))
      (node (ref "D6") (pin "1") (pinfunction "A_1") (pintype "passive"))
      (node (ref "D7") (pin "1") (pinfunction "A_1") (pintype "passive"))
      (node (ref "D8") (pin "1") (pinfunction "A_1") (pintype "passive"))
      (node (ref "D9") (pin "1") (pinfunction "A_1") (pintype "passive"))
      (node (ref "LD1") (pin "3") (pinfunction "3_3") (pintype "passive"))
      (node (ref "LD10") (pin "3") (pinfunction "3_3") (pintype "passive"))
      (node (ref "LD11") (pin "3") (pinfunction "3_3") (pintype "passive"))
      (node (ref "LD12") (pin "3") (pinfunction "3_3") (pintype "passive"))
      (node (ref "LD13") (pin "3") (pinfunction "3_3") (pintype "passive"))
      (node (ref "LD14") (pin "3") (pinfunction "3_3") (pintype "passive"))
      (node (ref "LD15") (pin "3") (pinfunction "3_3") (pintype "passive"))
      (node (ref "LD16") (pin "3") (pinfunction "3_3") (pintype "passive"))
      (node (ref "LD17") (pin "3") (pinfunction "3_3") (pintype "passive"))
      (node (ref "LD18") (pin "3") (pinfunction "3_3") (pintype "passive"))
      (node (ref "LD19") (pin "3") (pinfunction "3_3") (pintype "passive"))
      (node (ref "LD2") (pin "3") (pinfunction "3_3") (pintype "passive"))
      (node (ref "LD20") (pin "3") (pinfunction "3_3") (pintype "passive"))
      (node (ref "LD21") (pin "3") (pinfunction "3_3") (pintype "passive"))
      (node (ref "LD22") (pin "3") (pinfunction "3_3") (pintype "passive"))
      (node (ref "LD23") (pin "3") (pinfunction "3_3") (pintype "passive"))
      (node (ref "LD24") (pin "3") (pinfunction "3_3") (pintype "passive"))
      (node (ref "LD25") (pin "3") (pinfunction "3_3") (pintype "passive"))
      (node (ref "LD26") (pin "3") (pinfunction "3_3") (pintype "passive"))
      (node (ref "LD27") (pin "3") (pinfunction "3_3") (pintype "passive"))
      (node (ref "LD28") (pin "3") (pinfunction "3_3") (pintype "passive"))
      (node (ref "LD29") (pin "3") (pinfunction "3_3") (pintype "passive"))
      (node (ref "LD3") (pin "3") (pinfunction "3_3") (pintype "passive"))
      (node (ref "LD30") (pin "3") (pinfunction "3_3") (pintype "passive"))
      (node (ref "LD31") (pin "3") (pinfunction "3_3") (pintype "passive"))
      (node (ref "LD32") (pin "3") (pinfunction "3_3") (pintype "passive"))
      (node (ref "LD33") (pin "3") (pinfunction "3_3") (pintype "passive"))
      (node (ref "LD34") (pin "3") (pinfunction "3_3") (pintype "passive"))
      (node (ref "LD35") (pin "3") (pinfunction "3_3") (pintype "passive"))
      (node (ref "LD36") (pin "3") (pinfunction "3_3") (pintype "passive"))
      (node (ref "LD4") (pin "3") (pinfunction "3_3") (pintype "passive"))
      (node (ref "LD5") (pin "3") (pinfunction "3_3") (pintype "passive"))
      (node (ref "LD6") (pin "3") (pinfunction "3_3") (pintype "passive"))
      (node (ref "LD7") (pin "3") (pinfunction "3_3") (pintype "passive"))
      (node (ref "LD8") (pin "3") (pinfunction "3_3") (pintype "passive"))
      (node (ref "LD9") (pin "3") (pinfunction "3_3") (pintype "passive"))
      (node (ref "TP13") (pin "1") (pintype "power_in"))
    )
    (net (code "14") (name "Net-(C23-Pad1)") (class "Default")
      (node (ref "C23") (pin "1") (pinfunction "1_1") (pintype "passive"))
      (node (ref "C24") (pin "2") (pinfunction "2_2") (pintype "passive"))
    )
    (net (code "15") (name "Net-(C25-Pad1)") (class "Default")
      (node (ref "C25") (pin "1") (pinfunction "1_1") (pintype "passive"))
      (node (ref "C26") (pin "2") (pinfunction "2_2") (pintype "passive"))
    )
    (net (code "16") (name "Net-(C27-Pad1)") (class "Default")
      (node (ref "C27") (pin "1") (pinfunction "1_1") (pintype "passive"))
      (node (ref "C28") (pin "2") (pinfunction "2_2") (pintype "passive"))
    )
    (net (code "17") (name "Net-(C29-Pad1)") (class "Default")
      (node (ref "C29") (pin "1") (pinfunction "1_1") (pintype "passive"))
      (node (ref "C30") (pin "2") (pinfunction "2_2") (pintype "passive"))
    )
    (net (code "18") (name "Net-(C31-Pad1)") (class "Default")
      (node (ref "C31") (pin "1") (pinfunction "1_1") (pintype "passive"))
      (node (ref "C32") (pin "2") (pinfunction "2_2") (pintype "passive"))
    )
    (net (code "19") (name "Net-(C33-Pad1)") (class "Default")
      (node (ref "C33") (pin "1") (pinfunction "1_1") (pintype "passive"))
      (node (ref "C34") (pin "2") (pinfunction "2_2") (pintype "passive"))
    )
    (net (code "20") (name "Net-(D1-K)") (class "Default")
      (node (ref "D1") (pin "2") (pinfunction "K_2") (pintype "passive"))
      (node (ref "LD1") (pin "1") (pinfunction "1_1") (pintype "passive"))
      (node (ref "TP14") (pin "1") (pintype "power_in"))
      (node (ref "U5") (pin "2") (pinfunction "S1_2") (pintype "bidirectional"))
    )
    (net (code "21") (name "Net-(D2-K)") (class "Default")
      (node (ref "D2") (pin "2") (pinfunction "K_2") (pintype "passive"))
      (node (ref "LD7") (pin "1") (pinfunction "1_1") (pintype "passive"))
      (node (ref "U7") (pin "2") (pinfunction "S1_2") (pintype "bidirectional"))
    )
    (net (code "22") (name "Net-(D3-K)") (class "Default")
      (node (ref "D3") (pin "2") (pinfunction "K_2") (pintype "passive"))
      (node (ref "LD6") (pin "1") (pinfunction "1_1") (pintype "passive"))
      (node (ref "U5") (pin "13") (pinfunction "S6_13") (pintype "bidirectional"))
    )
    (net (code "23") (name "Net-(D4-K)") (class "Default")
      (node (ref "D4") (pin "2") (pinfunction "K_2") (pintype "passive"))
      (node (ref "LD2") (pin "1") (pinfunction "1_1") (pintype "passive"))
      (node (ref "U5") (pin "4") (pinfunction "S2_4") (pintype "bidirectional"))
    )
    (net (code "24") (name "Net-(D5-K)") (class "Default")
      (node (ref "D5") (pin "2") (pinfunction "K_2") (pintype "passive"))
      (node (ref "LD5") (pin "1") (pinfunction "1_1") (pintype "passive"))
      (node (ref "U5") (pin "11") (pinfunction "S5_11") (pintype "bidirectional"))
    )
    (net (code "25") (name "Net-(D6-K)") (class "Default")
      (node (ref "D6") (pin "2") (pinfunction "K_2") (pintype "passive"))
      (node (ref "LD3") (pin "1") (pinfunction "1_1") (pintype "passive"))
      (node (ref "U5") (pin "6") (pinfunction "S3_6") (pintype "bidirectional"))
    )
    (net (code "26") (name "Net-(D7-K)") (class "Default")
      (node (ref "D7") (pin "2") (pinfunction "K_2") (pintype "passive"))
      (node (ref "LD8") (pin "1") (pinfunction "1_1") (pintype "passive"))
      (node (ref "U7") (pin "4") (pinfunction "S2_4") (pintype "bidirectional"))
    )
    (net (code "27") (name "Net-(D8-K)") (class "Default")
      (node (ref "D8") (pin "2") (pinfunction "K_2") (pintype "passive"))
      (node (ref "LD4") (pin "1") (pinfunction "1_1") (pintype "passive"))
      (node (ref "U5") (pin "8") (pinfunction "S4_8") (pintype "bidirectional"))
    )
    (net (code "28") (name "Net-(D9-K)") (class "Default")
      (node (ref "D9") (pin "2") (pinfunction "K_2") (pintype "passive"))
      (node (ref "LD13") (pin "1") (pinfunction "1_1") (pintype "passive"))
      (node (ref "U10") (pin "2") (pinfunction "S1_2") (pintype "bidirectional"))
    )
    (net (code "29") (name "Net-(D10-K)") (class "Default")
      (node (ref "D10") (pin "2") (pinfunction "K_2") (pintype "passive"))
      (node (ref "LD9") (pin "1") (pinfunction "1_1") (pintype "passive"))
      (node (ref "U7") (pin "6") (pinfunction "S3_6") (pintype "bidirectional"))
    )
    (net (code "30") (name "Net-(D11-K)") (class "Default")
      (node (ref "D11") (pin "2") (pinfunction "K_2") (pintype "passive"))
      (node (ref "LD14") (pin "1") (pinfunction "1_1") (pintype "passive"))
      (node (ref "U10") (pin "4") (pinfunction "S2_4") (pintype "bidirectional"))
    )
    (net (code "31") (name "Net-(D12-K)") (class "Default")
      (node (ref "D12") (pin "2") (pinfunction "K_2") (pintype "passive"))
      (node (ref "LD10") (pin "1") (pinfunction "1_1") (pintype "passive"))
      (node (ref "U7") (pin "8") (pinfunction "S4_8") (pintype "bidirectional"))
    )
    (net (code "32") (name "Net-(D13-K)") (class "Default")
      (node (ref "D13") (pin "2") (pinfunction "K_2") (pintype "passive"))
      (node (ref "LD15") (pin "1") (pinfunction "1_1") (pintype "passive"))
      (node (ref "U10") (pin "6") (pinfunction "S3_6") (pintype "bidirectional"))
    )
    (net (code "33") (name "Net-(D14-K)") (class "Default")
      (node (ref "D14") (pin "2") (pinfunction "K_2") (pintype "passive"))
      (node (ref "LD11") (pin "1") (pinfunction "1_1") (pintype "passive"))
      (node (ref "U7") (pin "11") (pinfunction "S5_11") (pintype "bidirectional"))
    )
    (net (code "34") (name "Net-(D15-K)") (class "Default")
      (node (ref "D15") (pin "2") (pinfunction "K_2") (pintype "passive"))
      (node (ref "LD16") (pin "1") (pinfunction "1_1") (pintype "passive"))
      (node (ref "U10") (pin "8") (pinfunction "S4_8") (pintype "bidirectional"))
    )
    (net (code "35") (name "Net-(D16-K)") (class "Default")
      (node (ref "D16") (pin "2") (pinfunction "K_2") (pintype "passive"))
      (node (ref "LD12") (pin "1") (pinfunction "1_1") (pintype "passive"))
      (node (ref "U7") (pin "13") (pinfunction "S6_13") (pintype "bidirectional"))
    )
    (net (code "36") (name "Net-(D17-K)") (class "Default")
      (node (ref "D17") (pin "2") (pinfunction "K_2") (pintype "passive"))
      (node (ref "LD21") (pin "1") (pinfunction "1_1") (pintype "passive"))
      (node (ref "U6") (pin "6") (pinfunction "S3_6") (pintype "bidirectional"))
    )
    (net (code "37") (name "Net-(D18-K)") (class "Default")
      (node (ref "D18") (pin "2") (pinfunction "K_2") (pintype "passive"))
      (node (ref "LD17") (pin "1") (pinfunction "1_1") (pintype "passive"))
      (node (ref "U10") (pin "11") (pinfunction "S5_11") (pintype "bidirectional"))
    )
    (net (code "38") (name "Net-(D19-K)") (class "Default")
      (node (ref "D19") (pin "2") (pinfunction "K_2") (pintype "passive"))
      (node (ref "LD18") (pin "1") (pinfunction "1_1") (pintype "passive"))
      (node (ref "U10") (pin "13") (pinfunction "S6_13") (pintype "bidirectional"))
    )
    (net (code "39") (name "Net-(D20-K)") (class "Default")
      (node (ref "D20") (pin "2") (pinfunction "K_2") (pintype "passive"))
      (node (ref "LD22") (pin "1") (pinfunction "1_1") (pintype "passive"))
      (node (ref "U6") (pin "8") (pinfunction "S4_8") (pintype "bidirectional"))
    )
    (net (code "40") (name "Net-(D21-K)") (class "Default")
      (node (ref "D21") (pin "2") (pinfunction "K_2") (pintype "passive"))
      (node (ref "LD23") (pin "1") (pinfunction "1_1") (pintype "passive"))
      (node (ref "U6") (pin "11") (pinfunction "S5_11") (pintype "bidirectional"))
    )
    (net (code "41") (name "Net-(D22-K)") (class "Default")
      (node (ref "D22") (pin "2") (pinfunction "K_2") (pintype "passive"))
      (node (ref "LD19") (pin "1") (pinfunction "1_1") (pintype "passive"))
      (node (ref "U6") (pin "2") (pinfunction "S1_2") (pintype "bidirectional"))
    )
    (net (code "42") (name "Net-(D23-K)") (class "Default")
      (node (ref "D23") (pin "2") (pinfunction "K_2") (pintype "passive"))
      (node (ref "LD24") (pin "1") (pinfunction "1_1") (pintype "passive"))
      (node (ref "U6") (pin "13") (pinfunction "S6_13") (pintype "bidirectional"))
    )
    (net (code "43") (name "Net-(D24-K)") (class "Default")
      (node (ref "D24") (pin "2") (pinfunction "K_2") (pintype "passive"))
      (node (ref "LD20") (pin "1") (pinfunction "1_1") (pintype "passive"))
      (node (ref "U6") (pin "4") (pinfunction "S2_4") (pintype "bidirectional"))
    )
    (net (code "44") (name "Net-(D25-K)") (class "Default")
      (node (ref "D25") (pin "2") (pinfunction "K_2") (pintype "passive"))
      (node (ref "LD29") (pin "1") (pinfunction "1_1") (pintype "passive"))
      (node (ref "U8") (pin "11") (pinfunction "S5_11") (pintype "bidirectional"))
    )
    (net (code "45") (name "Net-(D26-K)") (class "Default")
      (node (ref "D26") (pin "2") (pinfunction "K_2") (pintype "passive"))
      (node (ref "LD25") (pin "1") (pinfunction "1_1") (pintype "passive"))
      (node (ref "U8") (pin "2") (pinfunction "S1_2") (pintype "bidirectional"))
    )
    (net (code "46") (name "Net-(D27-K)") (class "Default")
      (node (ref "D27") (pin "2") (pinfunction "K_2") (pintype "passive"))
      (node (ref "LD26") (pin "1") (pinfunction "1_1") (pintype "passive"))
      (node (ref "U8") (pin "4") (pinfunction "S2_4") (pintype "bidirectional"))
    )
    (net (code "47") (name "Net-(D28-K)") (class "Default")
      (node (ref "D28") (pin "2") (pinfunction "K_2") (pintype "passive"))
      (node (ref "LD30") (pin "1") (pinfunction "1_1") (pintype "passive"))
      (node (ref "U8") (pin "13") (pinfunction "S6_13") (pintype "bidirectional"))
    )
    (net (code "48") (name "Net-(D29-K)") (class "Default")
      (node (ref "D29") (pin "2") (pinfunction "K_2") (pintype "passive"))
      (node (ref "LD31") (pin "1") (pinfunction "1_1") (pintype "passive"))
      (node (ref "U9") (pin "2") (pinfunction "S1_2") (pintype "bidirectional"))
    )
    (net (code "49") (name "Net-(D30-K)") (class "Default")
      (node (ref "D30") (pin "2") (pinfunction "K_2") (pintype "passive"))
      (node (ref "LD27") (pin "1") (pinfunction "1_1") (pintype "passive"))
      (node (ref "U8") (pin "6") (pinfunction "S3_6") (pintype "bidirectional"))
    )
    (net (code "50") (name "Net-(D31-K)") (class "Default")
      (node (ref "D31") (pin "2") (pinfunction "K_2") (pintype "passive"))
      (node (ref "LD32") (pin "1") (pinfunction "1_1") (pintype "passive"))
      (node (ref "U9") (pin "4") (pinfunction "S2_4") (pintype "bidirectional"))
    )
    (net (code "51") (name "Net-(D32-K)") (class "Default")
      (node (ref "D32") (pin "2") (pinfunction "K_2") (pintype "passive"))
      (node (ref "LD28") (pin "1") (pinfunction "1_1") (pintype "passive"))
      (node (ref "U8") (pin "8") (pinfunction "S4_8") (pintype "bidirectional"))
    )
    (net (code "52") (name "Net-(D34-K)") (class "Default")
      (node (ref "D34") (pin "2") (pinfunction "K_2") (pintype "passive"))
      (node (ref "LD33") (pin "1") (pinfunction "1_1") (pintype "passive"))
      (node (ref "U9") (pin "6") (pinfunction "S3_6") (pintype "bidirectional"))
    )
    (net (code "53") (name "Net-(D35-K)") (class "Default")
      (node (ref "D35") (pin "2") (pinfunction "K_2") (pintype "passive"))
      (node (ref "LD34") (pin "1") (pinfunction "1_1") (pintype "passive"))
      (node (ref "U9") (pin "8") (pinfunction "S4_8") (pintype "bidirectional"))
    )
    (net (code "54") (name "Net-(D38-K)") (class "Default")
      (node (ref "D38") (pin "2") (pinfunction "K_2") (pintype "passive"))
      (node (ref "LD35") (pin "1") (pinfunction "1_1") (pintype "passive"))
      (node (ref "U9") (pin "11") (pinfunction "S5_11") (pintype "bidirectional"))
    )
    (net (code "55") (name "Net-(D40-K)") (class "Default")
      (node (ref "D40") (pin "2") (pinfunction "K_2") (pintype "passive"))
      (node (ref "LD36") (pin "1") (pinfunction "1_1") (pintype "passive"))
      (node (ref "U9") (pin "13") (pinfunction "S6_13") (pintype "bidirectional"))
    )
    (net (code "56") (name "Net-(U5-*RESET{slash}VL)") (class "Default")
      (node (ref "R19") (pin "1") (pinfunction "1_1") (pintype "passive"))
      (node (ref "U5") (pin "20") (pinfunction "*RESET/VL_20") (pintype "bidirectional"))
    )
    (net (code "57") (name "Net-(U6-*RESET{slash}VL)") (class "Default")
      (node (ref "R17") (pin "1") (pinfunction "1_1") (pintype "passive"))
      (node (ref "U6") (pin "20") (pinfunction "*RESET/VL_20") (pintype "bidirectional"))
    )
    (net (code "58") (name "Net-(U7-*RESET{slash}VL)") (class "Default")
      (node (ref "R15") (pin "1") (pinfunction "1_1") (pintype "passive"))
      (node (ref "U7") (pin "20") (pinfunction "*RESET/VL_20") (pintype "bidirectional"))
    )
    (net (code "59") (name "Net-(U8-*RESET{slash}VL)") (class "Default")
      (node (ref "R18") (pin "1") (pinfunction "1_1") (pintype "passive"))
      (node (ref "U8") (pin "20") (pinfunction "*RESET/VL_20") (pintype "bidirectional"))
    )
    (net (code "60") (name "Net-(U9-*RESET{slash}VL)") (class "Default")
      (node (ref "R36") (pin "1") (pinfunction "1_1") (pintype "passive"))
      (node (ref "U9") (pin "20") (pinfunction "*RESET/VL_20") (pintype "bidirectional"))
    )
    (net (code "61") (name "Net-(U10-*RESET{slash}VL)") (class "Default")
      (node (ref "R16") (pin "1") (pinfunction "1_1") (pintype "passive"))
      (node (ref "U10") (pin "20") (pinfunction "*RESET/VL_20") (pintype "bidirectional"))
    )
    (net (code "62") (name "unconnected-(U5-D7-Pad14)") (class "Default")
      (node (ref "U5") (pin "14") (pinfunction "D7_14") (pintype "bidirectional+no_connect"))
    )
    (net (code "63") (name "unconnected-(U5-D8-Pad16)") (class "Default")
      (node (ref "U5") (pin "16") (pinfunction "D8_16") (pintype "bidirectional+no_connect"))
    )
    (net (code "64") (name "unconnected-(U5-S7-Pad15)") (class "Default")
      (node (ref "U5") (pin "15") (pinfunction "S7_15") (pintype "bidirectional+no_connect"))
    )
    (net (code "65") (name "unconnected-(U5-S8-Pad17)") (class "Default")
      (node (ref "U5") (pin "17") (pinfunction "S8_17") (pintype "bidirectional+no_connect"))
    )
    (net (code "66") (name "unconnected-(U6-D7-Pad14)") (class "Default")
      (node (ref "U6") (pin "14") (pinfunction "D7_14") (pintype "bidirectional+no_connect"))
    )
    (net (code "67") (name "unconnected-(U6-D8-Pad16)") (class "Default")
      (node (ref "U6") (pin "16") (pinfunction "D8_16") (pintype "bidirectional+no_connect"))
    )
    (net (code "68") (name "unconnected-(U6-S7-Pad15)") (class "Default")
      (node (ref "U6") (pin "15") (pinfunction "S7_15") (pintype "bidirectional+no_connect"))
    )
    (net (code "69") (name "unconnected-(U6-S8-Pad17)") (class "Default")
      (node (ref "U6") (pin "17") (pinfunction "S8_17") (pintype "bidirectional+no_connect"))
    )
    (net (code "70") (name "unconnected-(U7-D7-Pad14)") (class "Default")
      (node (ref "U7") (pin "14") (pinfunction "D7_14") (pintype "bidirectional+no_connect"))
    )
    (net (code "71") (name "unconnected-(U7-D8-Pad16)") (class "Default")
      (node (ref "U7") (pin "16") (pinfunction "D8_16") (pintype "bidirectional+no_connect"))
    )
    (net (code "72") (name "unconnected-(U7-S7-Pad15)") (class "Default")
      (node (ref "U7") (pin "15") (pinfunction "S7_15") (pintype "bidirectional+no_connect"))
    )
    (net (code "73") (name "unconnected-(U7-S8-Pad17)") (class "Default")
      (node (ref "U7") (pin "17") (pinfunction "S8_17") (pintype "bidirectional+no_connect"))
    )
    (net (code "74") (name "unconnected-(U8-D7-Pad14)") (class "Default")
      (node (ref "U8") (pin "14") (pinfunction "D7_14") (pintype "bidirectional+no_connect"))
    )
    (net (code "75") (name "unconnected-(U8-D8-Pad16)") (class "Default")
      (node (ref "U8") (pin "16") (pinfunction "D8_16") (pintype "bidirectional+no_connect"))
    )
    (net (code "76") (name "unconnected-(U8-S7-Pad15)") (class "Default")
      (node (ref "U8") (pin "15") (pinfunction "S7_15") (pintype "bidirectional+no_connect"))
    )
    (net (code "77") (name "unconnected-(U8-S8-Pad17)") (class "Default")
      (node (ref "U8") (pin "17") (pinfunction "S8_17") (pintype "bidirectional+no_connect"))
    )
    (net (code "78") (name "unconnected-(U9-D7-Pad14)") (class "Default")
      (node (ref "U9") (pin "14") (pinfunction "D7_14") (pintype "bidirectional+no_connect"))
    )
    (net (code "79") (name "unconnected-(U9-D8-Pad16)") (class "Default")
      (node (ref "U9") (pin "16") (pinfunction "D8_16") (pintype "bidirectional+no_connect"))
    )
    (net (code "80") (name "unconnected-(U9-S7-Pad15)") (class "Default")
      (node (ref "U9") (pin "15") (pinfunction "S7_15") (pintype "bidirectional+no_connect"))
    )
    (net (code "81") (name "unconnected-(U9-S8-Pad17)") (class "Default")
      (node (ref "U9") (pin "17") (pinfunction "S8_17") (pintype "bidirectional+no_connect"))
    )
    (net (code "82") (name "unconnected-(U10-D7-Pad14)") (class "Default")
      (node (ref "U10") (pin "14") (pinfunction "D7_14") (pintype "bidirectional+no_connect"))
    )
    (net (code "83") (name "unconnected-(U10-D8-Pad16)") (class "Default")
      (node (ref "U10") (pin "16") (pinfunction "D8_16") (pintype "bidirectional+no_connect"))
    )
    (net (code "84") (name "unconnected-(U10-S7-Pad15)") (class "Default")
      (node (ref "U10") (pin "15") (pinfunction "S7_15") (pintype "bidirectional+no_connect"))
    )
    (net (code "85") (name "unconnected-(U10-S8-Pad17)") (class "Default")
      (node (ref "U10") (pin "17") (pinfunction "S8_17") (pintype "bidirectional+no_connect"))
    )
  )
)
